# Bipolar_HCP.net
KiCad netlist of a schematic drawn in Altium Designer
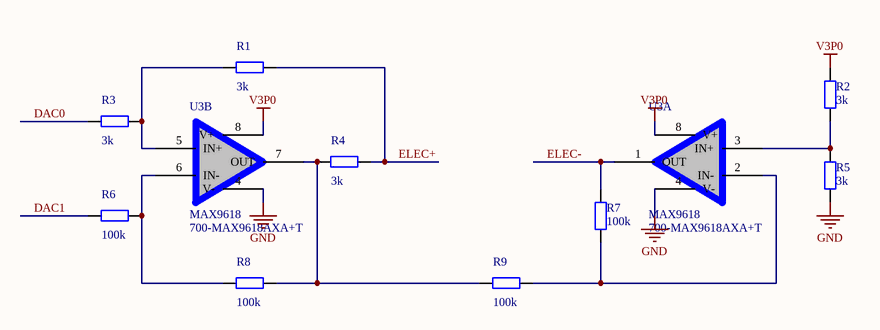
[diagram p0: Bipolar_HCP.SchDoc]

(export (version "E")
  (design (tool "Eeschema 10.0.6"))
  (components
    (comp (ref "R1")
      (value "3k")
      (footprint "0402")
      (description "Resistor")
      (fields (field (name "Comment") "Res2"))
      (libsource (lib "") (part "Res2_1"))
    )
    (comp (ref "R2")
      (value "3k")
      (footprint "0201")
      (description "Resistor")
      (fields (field (name "Comment") "Res2"))
      (libsource (lib "Miscellaneous Devices") (part "Res2"))
    )
    (comp (ref "R3")
      (value "3k")
      (footprint "0402")
      (description "Resistor")
      (fields (field (name "Comment") "Res2"))
      (libsource (lib "") (part "Res2_1"))
    )
    (comp (ref "R4")
      (value "3k")
      (footprint "0201")
      (description "Resistor")
      (fields (field (name "Comment") "Res2"))
      (libsource (lib "") (part "Res2_1"))
    )
    (comp (ref "R5")
      (value "3k")
      (footprint "0201")
      (description "Resistor")
      (fields (field (name "Comment") "Res2"))
      (libsource (lib "Miscellaneous Devices") (part "Res2"))
    )
    (comp (ref "R6")
      (value "100k")
      (footprint "0201")
      (description "Resistor")
      (fields (field (name "Comment") "Res2"))
      (libsource (lib "") (part "Res2_1"))
    )
    (comp (ref "R7")
      (value "100k")
      (footprint "0201")
      (description "Resistor")
      (fields (field (name "Comment") "Res2"))
      (libsource (lib "Miscellaneous Devices") (part "Res2"))
    )
    (comp (ref "R8")
      (value "100k")
      (footprint "0201")
      (description "Resistor")
      (fields (field (name "Comment") "Res2"))
      (libsource (lib "") (part "Res2_1"))
    )
    (comp (ref "R9")
      (value "100k")
      (footprint "0201")
      (description "Resistor")
      (fields (field (name "Comment") "Res2"))
      (libsource (lib "") (part "Res2_1"))
    )
    (comp (ref "U3")
      (value "MAX9618")
      (footprint "MAX_X8CN_SC70_8")
      (description "Op Amps Dual Auto-Zero Op Amp")
      (fields
        (field (name "MANUFACTURER") "Maxim Integrated Products")
        (field (name "MANUFACTURER PART NUMBER") "MAX9618AXA+T")
        (field (name "SUPPLIER PART NUMBER 1") "700-MAX9618AXA+T")
      )
      (libsource (lib "custom") (part "MAX9618"))
    )
  )
  (nets
    (net (code "1") (name "/DAC0") (class "Default")
      (node (ref "R3") (pin "2") (pinfunction "2_2") (pintype "passive"))
    )
    (net (code "2") (name "/DAC1") (class "Default")
      (node (ref "R6") (pin "2") (pinfunction "2_2") (pintype "passive"))
    )
    (net (code "3") (name "/ELEC+") (class "Default")
      (node (ref "R1") (pin "1") (pinfunction "1_1") (pintype "passive"))
      (node (ref "R4") (pin "1") (pinfunction "1_1") (pintype "passive"))
    )
    (net (code "4") (name "/ELEC-") (class "Default")
      (node (ref "R7") (pin "1") (pinfunction "1_1") (pintype "passive"))
      (node (ref "U3") (pin "1") (pinfunction "OUT_1") (pintype "passive"))
    )
    (net (code "5") (name "GND") (class "Default")
      (node (ref "R5") (pin "2") (pinfunction "2_2") (pintype "passive"))
      (node (ref "U3") (pin "4") (pinfunction "V-_4") (pintype "passive"))
    )
    (net (code "6") (name "Net-(U3A-IN+)") (class "Default")
      (node (ref "R2") (pin "2") (pinfunction "2_2") (pintype "passive"))
      (node (ref "R5") (pin "1") (pinfunction "1_1") (pintype "passive"))
      (node (ref "U3") (pin "3") (pinfunction "IN+_3") (pintype "passive"))
    )
    (net (code "7") (name "Net-(U3A-IN-)") (class "Default")
      (node (ref "R7") (pin "2") (pinfunction "2_2") (pintype "passive"))
      (node (ref "R9") (pin "1") (pinfunction "1_1") (pintype "passive"))
      (node (ref "U3") (pin "2") (pinfunction "IN-_2") (pintype "passive"))
    )
    (net (code "8") (name "Net-(U3B-IN+)") (class "Default")
      (node (ref "R1") (pin "2") (pinfunction "2_2") (pintype "passive"))
      (node (ref "R3") (pin "1") (pinfunction "1_1") (pintype "passive"))
      (node (ref "U3") (pin "5") (pinfunction "IN+_5") (pintype "passive"))
    )
    (net (code "9") (name "Net-(U3B-IN-)") (class "Default")
      (node (ref "R6") (pin "1") (pinfunction "1_1") (pintype "passive"))
      (node (ref "R8") (pin "2") (pinfunction "2_2") (pintype "passive"))
      (node (ref "U3") (pin "6") (pinfunction "IN-_6") (pintype "passive"))
    )
    (net (code "10") (name "Net-(U3B-OUT)") (class "Default")
      (node (ref "R4") (pin "2") (pinfunction "2_2") (pintype "passive"))
      (node (ref "R8") (pin "1") (pinfunction "1_1") (pintype "passive"))
      (node (ref "R9") (pin "2") (pinfunction "2_2") (pintype "passive"))
      (node (ref "U3") (pin "7") (pinfunction "OUT_7") (pintype "passive"))
    )
    (net (code "11") (name "V3P0") (class "Default")
      (node (ref "R2") (pin "1") (pinfunction "1_1") (pintype "passive"))
      (node (ref "U3") (pin "8") (pinfunction "V+_8") (pintype "passive"))
    )
  )
)
